# 42-PERIPHERAL_POWER_SUPPLY.net
KiCad netlist of a schematic drawn in Altium Designer
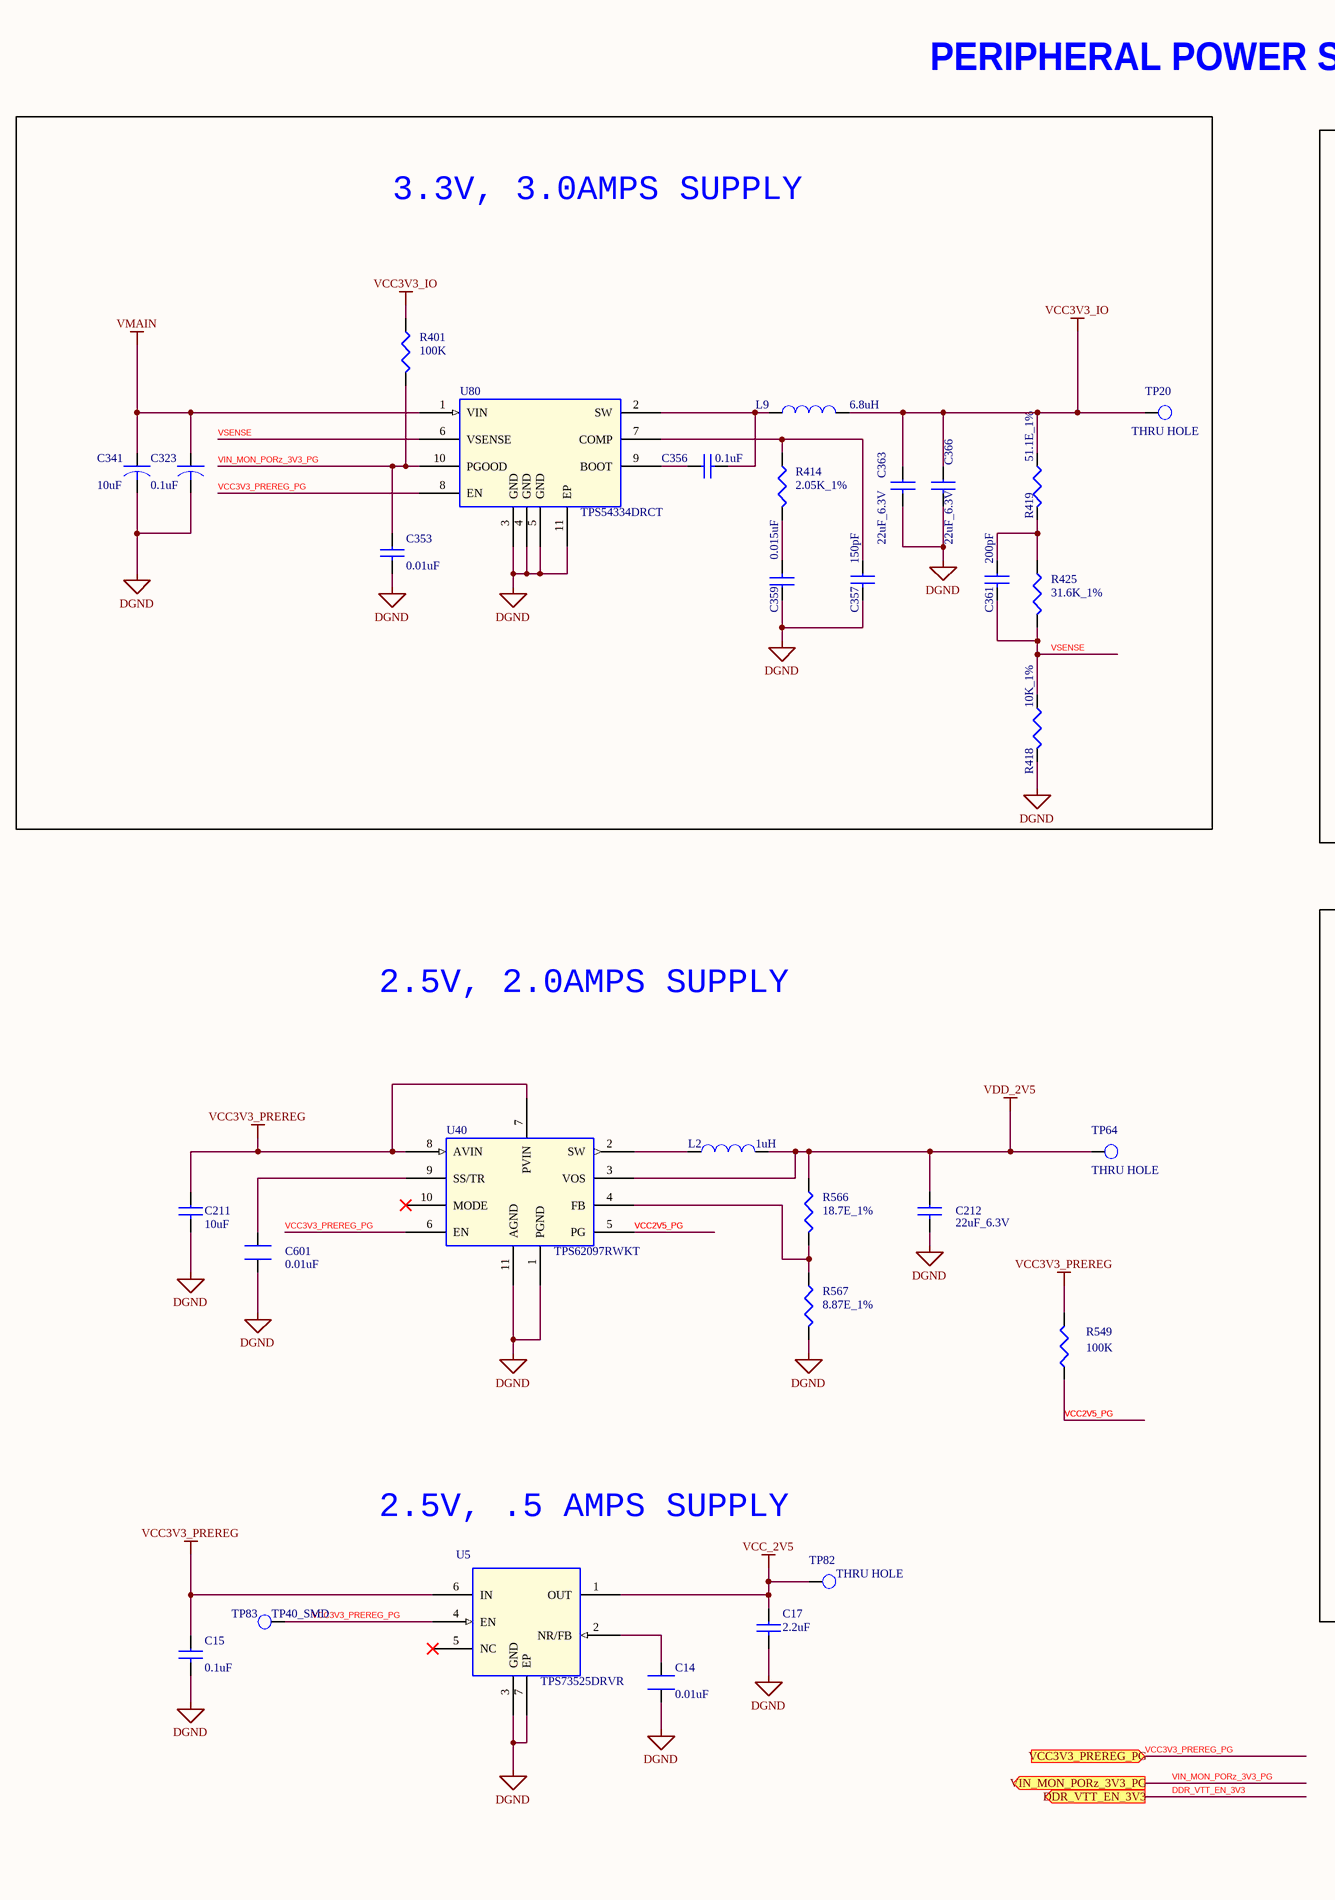
[diagram p0: 42-PERIPHERAL POWER SUPPLY.SchDoc, left]
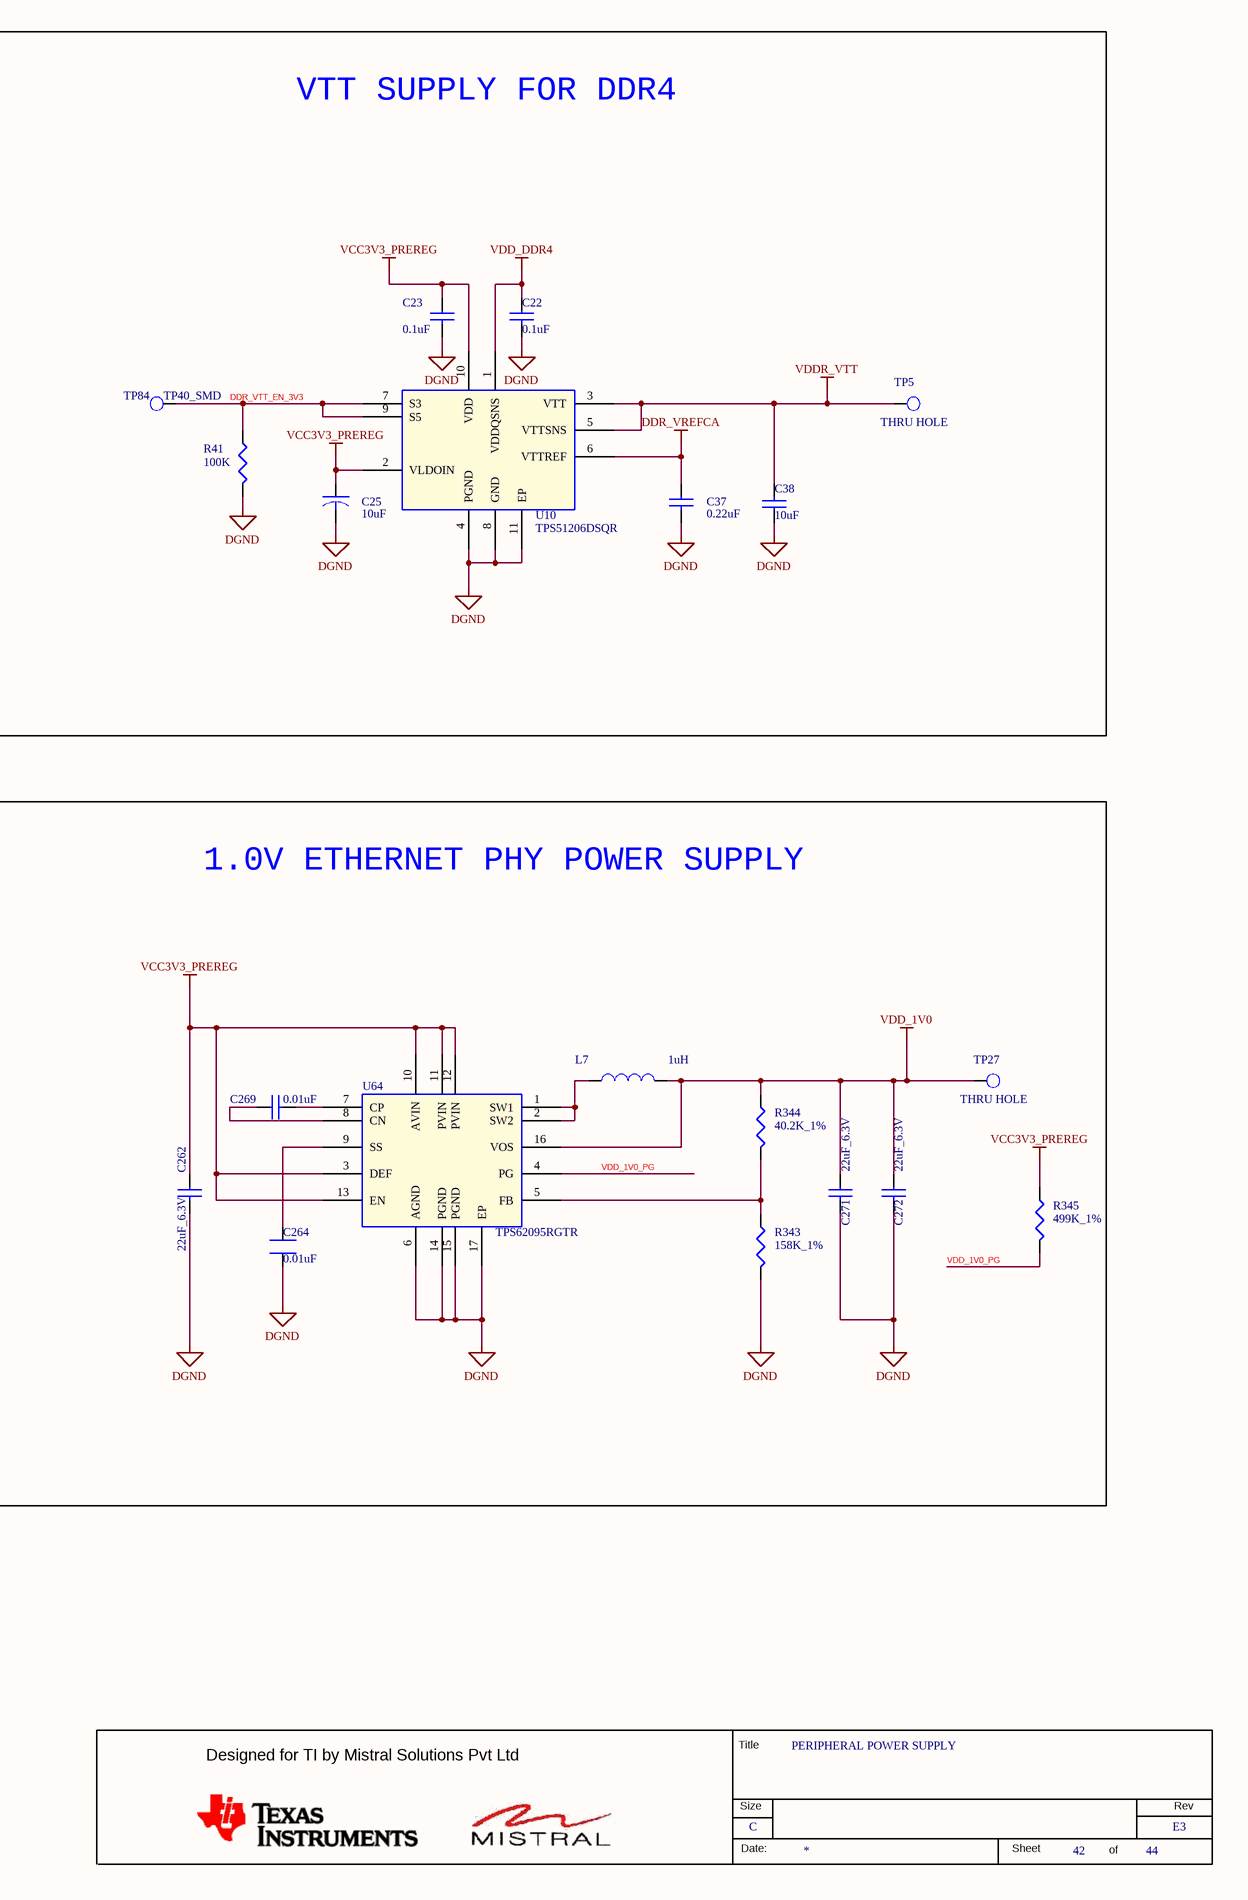
[diagram p1: 42-PERIPHERAL POWER SUPPLY.SchDoc, right]

(export (version "E")
  (design (tool "Eeschema 10.0.6"))
  (components
    (comp (ref "C14")
      (value "0.01uF")
      (footprint "TMDX654GPEVM_BRD:CAP0201_0-5")
      (description "CAP CERAMIC 0.01uF 25V 10% X5R 0201")
      (fields (field (name "DISTRIBUTOR_PART_NUMBER") "GRM033R61E103KA12J-ND") (field (name "VOLTAGE") "25V"))
      (libsource (lib "*") (part "CAP_Dup3"))
    )
    (comp (ref "C15")
      (value "0.1uF")
      (footprint "CAP0201_0-5")
      (description "CAP CERAMIC 0.1uF 16V 10% X5R 0201")
      (fields
        (field (name "MISTRAL PART NO") "120009030072-R")
        (field (name "MFR_PART_NUMBER") "GRM033R61C104KE84J")
      )
      (libsource (lib "*") (part "CAP_Dup5"))
    )
    (comp (ref "C17")
      (value "2.2uF")
      (footprint "CAP0402_0-75")
      (description "CAP CERAMIC 2.2uF 10V 20% X5R 0402")
      (fields
        (field (name "MISTRAL PART NO") "120018010016-R")
        (field (name "MFR_PART_NUMBER") "GRT155R61A225ME01D")
      )
      (libsource (lib "*") (part "CAP_Dup5"))
    )
    (comp (ref "C22")
      (value "0.1uF")
      (footprint "CAP0201_0-5")
      (description "CAP CERAMIC 0.1uF 16V 10% X5R 0201")
      (fields (field (name "DISTRIBUTOR_PART_NUMBER") "490-16742-1-ND") (field (name "VOLTAGE") "16V"))
      (libsource (lib "*") (part "CAP_Dup5"))
    )
    (comp (ref "C23")
      (value "0.1uF")
      (footprint "CAP0201_0-5")
      (description "CAP CERAMIC 0.1uF 16V 10% X5R 0201")
      (fields (field (name "DISTRIBUTOR_PART_NUMBER") "490-16742-1-ND") (field (name "VOLTAGE") "16V"))
      (libsource (lib "*") (part "CAP_Dup5"))
    )
    (comp (ref "C25")
      (value "10uF")
      (footprint "CAP0603_1")
      (description "CAP CERAMIC 10uF 10V 10% X5R 0603")
      (fields
        (field (name "MISTRAL PART NO") "120010080001-R")
        (field (name "MFR_PART_NUMBER") "0603ZD106KAT2A")
      )
      (libsource (lib "*") (part "CAP"))
    )
    (comp (ref "C37")
      (value "0.22uF")
      (footprint "CAP0402_0-75")
      (description "CAP CERAMIC 0.22uF 10V 10% X5R 0402")
      (fields
        (field (name "MISTRAL PART NO") "120009030090-R")
        (field (name "MFR_PART_NUMBER") "GRM155R61A224KE19D")
      )
      (libsource (lib "*") (part "CAP_Dup5"))
    )
    (comp (ref "C38")
      (value "10uF")
      (footprint "CAP0603_1")
      (description "CAP CERAMIC 10uF 10V 10% X5R 0603")
      (fields
        (field (name "MISTRAL PART NO") "120010080001-R")
        (field (name "MFR_PART_NUMBER") "0603ZD106KAT2A")
      )
      (libsource (lib "*") (part "CAP_Dup5"))
    )
    (comp (ref "C211")
      (value "10uF")
      (footprint "CAP0603_1")
      (description "CAP CERAMIC 10uF 10V 10% X5R 0603")
      (fields
        (field (name "MISTRAL PART NO") "120010080001-R")
        (field (name "MFR_PART_NUMBER") "0603ZD106KAT2A")
      )
      (libsource (lib "*") (part "CAP_Dup5"))
    )
    (comp (ref "C212")
      (value "22uF_6.3V")
      (footprint "CAP0603")
      (description "CAP CERAMIC 22uF 6.3V 20% X5R 0603")
      (fields
        (field (name "MISTRAL PART NO") "120015090007-R")
        (field (name "MFR_PART_NUMBER") "GRM188R60J226MEA0")
      )
      (libsource (lib "*") (part "CAP_Dup5"))
    )
    (comp (ref "C262")
      (value "22uF_6.3V")
      (footprint "CAP0603")
      (description "CAP CERAMIC 22uF 6.3V 20% X5R 0603")
      (fields (field (name "DISTRIBUTOR_PART_NUMBER") "490-7611-2-ND") (field (name "VOLTAGE") "6.3V"))
      (libsource (lib "*") (part "CAP_Dup5"))
    )
    (comp (ref "C264")
      (value "0.01uF")
      (footprint "TMDX654GPEVM_BRD:CAP0201_0-5")
      (description "CAP CERAMIC 0.01uF 25V 10% X5R 0201")
      (fields
        (field (name "MISTRAL PART NO") "120018010007-R")
        (field (name "MFR_PART_NUMBER") "GRM033R61E103KA12J")
      )
      (libsource (lib "*") (part "CAP_Dup3"))
    )
    (comp (ref "C269")
      (value "0.01uF")
      (footprint "CAP0201_0-5")
      (description "CAP CERAMIC 0.01uF 25V 10% X5R 0201")
      (fields
        (field (name "MISTRAL PART NO") "120018010007-R")
        (field (name "MFR_PART_NUMBER") "GRM033R61E103KA12J")
      )
      (libsource (lib "*") (part "CAP_Dup4"))
    )
    (comp (ref "C271")
      (value "22uF_6.3V")
      (footprint "CAP0603")
      (description "CAP CERAMIC 22uF 6.3V 20% X5R 0603")
      (fields
        (field (name "MISTRAL PART NO") "120015090007-R")
        (field (name "MFR_PART_NUMBER") "GRM188R60J226MEA0")
      )
      (libsource (lib "*") (part "CAP_Dup5"))
    )
    (comp (ref "C272")
      (value "22uF_6.3V")
      (footprint "CAP0603")
      (description "CAP CERAMIC 22uF 6.3V 20% X5R 0603")
      (fields (field (name "DISTRIBUTOR_PART_NUMBER") "490-7611-2-ND") (field (name "VOLTAGE") "6.3V"))
      (libsource (lib "*") (part "CAP_Dup5"))
    )
    (comp (ref "C323")
      (value "0.1uF")
      (footprint "CAP0603_1")
      (description "CAP CERAMIC 0.1uF 50V 20% X7R 0603")
      (fields (field (name "DISTRIBUTOR_PART_NUMBER") "399-7845-1-ND") (field (name "VOLTAGE") "50V"))
      (libsource (lib "*") (part "CAP_Dup1"))
    )
    (comp (ref "C341")
      (value "10uF")
      (footprint "CAP1206_2")
      (description "CAP CERAMIC 10uF 50V 20% X5R 1206")
      (fields (field (name "DISTRIBUTOR_PART_NUMBER") "490-10756-1-ND") (field (name "VOLTAGE") "50V"))
      (libsource (lib "*") (part "CAP"))
    )
    (comp (ref "C353")
      (value "0.01uF")
      (footprint "CAP0201_0-5")
      (description "CAP CERAMIC 0.01uF 25V 10% X5R 0201")
      (fields (field (name "DISTRIBUTOR_PART_NUMBER") "GRM033R61E103KA12J-ND") (field (name "VOLTAGE") "25V"))
      (libsource (lib "*") (part "CAP_Dup5"))
    )
    (comp (ref "C356")
      (value "0.1uF")
      (footprint "CAP0201_0-5")
      (description "CAP CERAMIC 0.1uF 16V 10% X5R 0201")
      (fields
        (field (name "MISTRAL PART NO") "120009030072-R")
        (field (name "MFR_PART_NUMBER") "GRM033R61C104KE84J")
      )
      (libsource (lib "*") (part "CAP_Dup5"))
    )
    (comp (ref "C357")
      (value "150pF")
      (footprint "CAP0402_0-75")
      (description "CAP CERAMIC 150pF 50V 10% X7R 0402")
      (fields
        (field (name "MISTRAL PART NO") "120018010022-R")
        (field (name "MFR_PART_NUMBER") "885012205056")
      )
      (libsource (lib "*") (part "CAP_Dup5"))
    )
    (comp (ref "C359")
      (value "0.015uF")
      (footprint "CAP0402")
      (description "CAP CERAMIC 0.015uF 16V 10% X7R 0402")
      (fields
        (field (name "MISTRAL PART NO") "120015120015-R")
        (field (name "MFR_PART_NUMBER") "GRM155R71C153KA01J")
      )
      (libsource (lib "*") (part "CAP_Dup5"))
    )
    (comp (ref "C361")
      (value "200pF")
      (footprint "CAP0402_0-75")
      (description "CAP CERAMIC 200pF 50V 5% C0G 0402")
      (fields (field (name "DISTRIBUTOR_PART_NUMBER") "490-3232-1-ND") (field (name "VOLTAGE") "50V"))
      (libsource (lib "*") (part "CAP_Dup5"))
    )
    (comp (ref "C363")
      (value "22uF_6.3V")
      (footprint "CAP0603")
      (description "CAP CERAMIC 22uF 6.3V 20% X5R 0603")
      (fields (field (name "DISTRIBUTOR_PART_NUMBER") "490-7611-2-ND") (field (name "VOLTAGE") "6.3V"))
      (libsource (lib "*") (part "CAP_Dup5"))
    )
    (comp (ref "C366")
      (value "22uF_6.3V")
      (footprint "CAP0603")
      (description "CAP CERAMIC 22uF 6.3V 20% X5R 0603")
      (fields (field (name "DISTRIBUTOR_PART_NUMBER") "490-7611-2-ND") (field (name "VOLTAGE") "6.3V"))
      (libsource (lib "*") (part "CAP_Dup5"))
    )
    (comp (ref "C601")
      (value "0.01uF")
      (footprint "TMDX654GPEVM_BRD:CAP0201_0-5")
      (description "CAP CERAMIC 0.01uF 25V 10% X5R 0201")
      (fields (field (name "DISTRIBUTOR_PART_NUMBER") "GRM033R61E103KA12J-ND") (field (name "VOLTAGE") "25V"))
      (libsource (lib "*") (part "CAP_Dup3"))
    )
    (comp (ref "L2")
      (value "1uH")
      (footprint "IND_IHLP2020AB_210X210_SMD_1-2")
      (description "IND POWER 1uH 4.4A 20% SMD")
      (fields
        (field (name "MISTRAL PART NO") "130017030015-R")
        (field (name "MFR_PART_NUMBER") "IHLP2020ABER1R0M01")
      )
      (libsource (lib "*") (part "INDUCTOR"))
    )
    (comp (ref "L7")
      (value "1uH")
      (footprint "IND_XFL4020_170X170_SMD_2-1")
      (description "IND POWER 1uH 8A 20% SMD")
      (fields (field (name "DISTRIBUTOR_PART_NUMBER") "994-XFL4020-102MEC") (field (name "VOLTAGE") "NA"))
      (libsource (lib "*") (part "INDUCTOR"))
    )
    (comp (ref "L9")
      (value "6.8uH")
      (footprint "IND_74439346068_260X270_SMD_6-1")
      (description "IND POWER 6.8uH 6.5A 20% SMD")
      (fields (field (name "DISTRIBUTOR_PART_NUMBER") "732-10705-1-ND") (field (name "VOLTAGE") "NA"))
      (libsource (lib "*") (part "INDUCTOR"))
    )
    (comp (ref "R41")
      (value "100K")
      (footprint "RES0402_0-5")
      (description "RES 100K 1/16W 5% 0402")
      (fields
        (field (name "MISTRAL PART NO") "110011060002-R")
        (field (name "MFR_PART_NUMBER") "CRCW0402100KJNED")
      )
      (libsource (lib "*") (part "RESISTOR_Dup4"))
    )
    (comp (ref "R343")
      (value "158K_1%")
      (footprint "RES0402_0-5")
      (description "RES 158K 1/16W 1% 0402")
      (fields (field (name "DISTRIBUTOR_PART_NUMBER") "YAG2990CT-ND") (field (name "VOLTAGE") "NA"))
      (libsource (lib "*") (part "RESISTOR_Dup5"))
    )
    (comp (ref "R344")
      (value "40.2K_1%")
      (footprint "RES0402_0-5")
      (description "RES 40.2K 1/16W 1% 0402")
      (fields
        (field (name "MISTRAL PART NO") "110009030811")
        (field (name "MFR_PART_NUMBER") "RC0402FR-0740K2L")
      )
      (libsource (lib "*") (part "RESISTOR_Dup5"))
    )
    (comp (ref "R345")
      (value "499K_1%")
      (footprint "RES0402")
      (description "RES 499K 1/16W 1% 0402")
      (fields
        (field (name "MISTRAL PART NO") "110009090015-P")
        (field (name "MFR_PART_NUMBER") "RC0402FR-07499KL")
      )
      (libsource (lib "*") (part "RESISTOR_Dup5"))
    )
    (comp (ref "R401")
      (value "100K")
      (footprint "RES0402_0-5")
      (description "RES 100K 1/16W 5% 0402")
      (fields
        (field (name "MISTRAL PART NO") "110011060002-R")
        (field (name "MFR_PART_NUMBER") "CRCW0402100KJNED")
      )
      (libsource (lib "*") (part "RESISTOR_Dup5"))
    )
    (comp (ref "R414")
      (value "2.05K_1%")
      (footprint "RES0402")
      (description "RES 2.05K 1/10W 1% 0402")
      (fields (field (name "DISTRIBUTOR_PART_NUMBER") "P2.05KLCT-ND") (field (name "VOLTAGE") "NA"))
      (libsource (lib "*") (part "RESISTOR_Dup5"))
    )
    (comp (ref "R418")
      (value "10K_1%")
      (footprint "RES0402_0-5")
      (description "RES 10K 1/16W 1% 0402")
      (fields (field (name "DISTRIBUTOR_PART_NUMBER") "311-10.0KLRTR-ND") (field (name "VOLTAGE") "NA"))
      (libsource (lib "*") (part "RESISTOR_Dup5"))
    )
    (comp (ref "R419")
      (value "51.1E_1%")
      (footprint "RES0402_0-5")
      (description "RES 51.1E 1/16W 1% 0402")
      (fields
        (field (name "MISTRAL PART NO") "110017060001-R")
        (field (name "MFR_PART_NUMBER") "RC0402FR-0751R1L")
      )
      (libsource (lib "*") (part "RESISTOR_Dup5"))
    )
    (comp (ref "R425")
      (value "31.6K_1%")
      (footprint "RES0402")
      (description "RES 31.6K 1/10W 1% 0402")
      (fields
        (field (name "MISTRAL PART NO") "110009030679-R")
        (field (name "MFR_PART_NUMBER") "ERJ-2RKF3162X")
      )
      (libsource (lib "*") (part "RESISTOR_Dup5"))
    )
    (comp (ref "R549")
      (value "100K")
      (footprint "RES0402_0-5")
      (description "RES 100K 1/16W 5% 0402")
      (fields (field (name "DISTRIBUTOR_PART_NUMBER") "541-100KJCT-ND") (field (name "VOLTAGE") "NA"))
      (libsource (lib "*") (part "RESISTOR_Dup5"))
    )
    (comp (ref "R566")
      (value "18.7E_1%")
      (footprint "RES0402")
      (description "RES 18.7E 1/16W 1% 0402")
      (fields
        (field (name "MISTRAL PART NO") "110010090023-P")
        (field (name "MFR_PART_NUMBER") "CRCW040218R7FKED")
      )
      (libsource (lib "*") (part "RESISTOR_Dup5"))
    )
    (comp (ref "R567")
      (value "8.87E_1%")
      (footprint "RES0402")
      (description "RES 8.87E 1/16W 1% 0402")
      (fields
        (field (name "MISTRAL PART NO") "110014010002-R")
        (field (name "MFR_PART_NUMBER") "CRCW04028R87FKED")
      )
      (libsource (lib "*") (part "RESISTOR_Dup5"))
    )
    (comp (ref "TP5")
      (value "THRU HOLE")
      (footprint "TP_40X65")
      (description "TESTPOINT 1.0MM DRILL PTH")
      (fields (field (name "DISTRIBUTOR_PART_NUMBER") "NA") (field (name "MFR_PART_NUMBER") "TP_40X65"))
      (libsource (lib "*") (part "TESTPOINT"))
    )
    (comp (ref "TP20")
      (value "THRU HOLE")
      (footprint "TP_40X65")
      (description "TESTPOINT 1.0MM DRILL PTH")
      (fields (field (name "DISTRIBUTOR_PART_NUMBER") "NA") (field (name "MFR_PART_NUMBER") "TP_40X65"))
      (libsource (lib "*") (part "TESTPOINT"))
    )
    (comp (ref "TP27")
      (value "THRU HOLE")
      (footprint "TP_40X65")
      (description "TESTPOINT 1.0MM DRILL PTH")
      (fields (field (name "DISTRIBUTOR_PART_NUMBER") "NA") (field (name "MFR_PART_NUMBER") "TP_40X65"))
      (libsource (lib "*") (part "TESTPOINT"))
    )
    (comp (ref "TP64")
      (value "THRU HOLE")
      (footprint "TP_40X65")
      (description "TESTPOINT 1.0MM DRILL PTH")
      (fields (field (name "MISTRAL PART NO") "130009030938") (field (name "MFR_PART_NUMBER") "TP_40X65"))
      (libsource (lib "*") (part "TESTPOINT"))
    )
    (comp (ref "TP82")
      (value "THRU HOLE")
      (footprint "TP_40X65")
      (description "TESTPOINT 1.0MM DRILL PTH")
      (fields (field (name "DISTRIBUTOR_PART_NUMBER") "NA") (field (name "MFR_PART_NUMBER") "TP_40X65"))
      (libsource (lib "*") (part "TESTPOINT"))
    )
    (comp (ref "TP83")
      (value "TP40_SMD")
      (footprint "TP40_SMD")
      (description "TESTPOINT CIR 40 SMD")
      (fields (field (name "MISTRAL PART NO") "130009030933") (field (name "DISTRIBUTOR_PART_NUMBER") "NA"))
      (libsource (lib "*") (part "TESTPOINT"))
    )
    (comp (ref "TP84")
      (value "TP40_SMD")
      (footprint "TP40_SMD")
      (description "TESTPOINT CIR 40 SMD")
      (fields (field (name "VOLTAGE") "NA") (field (name "MISTRAL PART NO") "130009030933"))
      (libsource (lib "*") (part "TESTPOINT"))
    )
    (comp (ref "U5")
      (value "TPS73525DRVR")
      (footprint "SON6_25-59_85X85_0-8")
      (description "IC 500mA LOW DROPOUT HIGH PSRR LINEAR REGULATOR SON6")
      (fields (field (name "DISTRIBUTOR_PART_NUMBER") "296-27480-1-ND") (field (name "VOLTAGE") "NA"))
      (libsource (lib "*") (part "TPS73501DRVR_SON6"))
    )
    (comp (ref "U10")
      (value "TPS51206DSQR")
      (footprint "DFN10_15-74_80X80_0-8")
      (description "IC SINK/SOURCE DDR TERMINATION REGULATOR WSON10")
      (fields (field (name "MISTRAL PART NO") "142017090016-R") (field (name "TOLERANCE") "NA"))
      (libsource (lib "*") (part "TPS51206DSQR_WSON10"))
    )
    (comp (ref "U40")
      (value "TPS62097RWKT")
      (footprint "VQFNHR11_TPS62097_80X80_1")
      (description "IC 2A SYNCHRONOUS STEP DOWN CONVERTER WITH IDCS CONTROL VQFN-HR11")
      (fields (field (name "MISTRAL PART NO") "142017090025-R") (field (name "TOLERANCE") "NA"))
      (libsource (lib "*") (part "TPS62097RWKT_VQFNHR11"))
    )
    (comp (ref "U64")
      (value "TPS62095RGTR")
      (footprint "QFN16_19-68_120X120_1")
      (description "IC 4A STEP DOWN CONVERTER WITH DCS CONTROL VQFN16")
      (fields (field (name "DISTRIBUTOR_PART_NUMBER") "296-40833-1-ND") (field (name "VOLTAGE") "NA"))
      (libsource (lib "*") (part "TPS62095RGTR_VQFN16"))
    )
    (comp (ref "U80")
      (value "TPS54334DRCT")
      (footprint "SON10_19-68_125X125_1")
      (description "IC 3A O/P CURRENT SYNCHRONOUS STEP DOWN VOLTAGE CONVERTER VSON10")
      (fields (field (name "DISTRIBUTOR_PART_NUMBER") "296-42172-2-ND") (field (name "VOLTAGE") "NA"))
      (libsource (lib "*") (part "TPS54334DRCT_VSON10"))
    )
  )
  (nets
    (net (code "1") (name "/DDR_VTT_EN_3V3") (class "Default")
      (node (ref "R41") (pin "1") (pinfunction "1_1") (pintype "passive"))
      (node (ref "TP84") (pin "1") (pinfunction "TP_1") (pintype "passive"))
      (node (ref "U10") (pin "7") (pinfunction "S3_7") (pintype "passive"))
      (node (ref "U10") (pin "9") (pinfunction "S5_9") (pintype "passive"))
    )
    (net (code "2") (name "/VCC2V5_PG") (class "Default")
      (node (ref "R549") (pin "1") (pinfunction "1_1") (pintype "passive"))
      (node (ref "U40") (pin "5") (pinfunction "PG_5") (pintype "passive"))
    )
    (net (code "3") (name "/VCC3V3_PREREG_PG") (class "Default")
      (node (ref "TP83") (pin "1") (pinfunction "TP_1") (pintype "passive"))
      (node (ref "U40") (pin "6") (pinfunction "EN_6") (pintype "passive"))
      (node (ref "U5") (pin "4") (pinfunction "EN_4") (pintype "input"))
      (node (ref "U80") (pin "8") (pinfunction "EN_8") (pintype "passive"))
    )
    (net (code "4") (name "/VDD_1V0_PG") (class "Default")
      (node (ref "R345") (pin "2") (pinfunction "2_2") (pintype "passive"))
      (node (ref "U64") (pin "4") (pinfunction "PG_4") (pintype "passive"))
    )
    (net (code "5") (name "/VIN_MON_PORz_3V3_PG") (class "Default")
      (node (ref "C353") (pin "1") (pinfunction "1_1") (pintype "passive"))
      (node (ref "R401") (pin "2") (pinfunction "2_2") (pintype "passive"))
      (node (ref "U80") (pin "10") (pinfunction "PGOOD_10") (pintype "passive"))
    )
    (net (code "6") (name "/VSENSE") (class "Default")
      (node (ref "C361") (pin "2") (pinfunction "2_2") (pintype "passive"))
      (node (ref "R418") (pin "1") (pinfunction "1_1") (pintype "passive"))
      (node (ref "R425") (pin "2") (pinfunction "2_2") (pintype "passive"))
      (node (ref "U80") (pin "6") (pinfunction "VSENSE_6") (pintype "passive"))
    )
    (net (code "7") (name "DDR_VREFCA") (class "Default")
      (node (ref "C37") (pin "1") (pinfunction "1_1") (pintype "passive"))
      (node (ref "U10") (pin "6") (pinfunction "VTTREF_6") (pintype "passive"))
    )
    (net (code "8") (name "DGND") (class "Default")
      (node (ref "C14") (pin "2") (pinfunction "2_2") (pintype "passive"))
      (node (ref "C15") (pin "2") (pinfunction "2_2") (pintype "passive"))
      (node (ref "C17") (pin "2") (pinfunction "2_2") (pintype "passive"))
      (node (ref "C211") (pin "2") (pinfunction "2_2") (pintype "passive"))
      (node (ref "C212") (pin "2") (pinfunction "2_2") (pintype "passive"))
      (node (ref "C22") (pin "2") (pinfunction "2_2") (pintype "passive"))
      (node (ref "C23") (pin "2") (pinfunction "2_2") (pintype "passive"))
      (node (ref "C25") (pin "2") (pinfunction "2_2") (pintype "passive"))
      (node (ref "C262") (pin "2") (pinfunction "2_2") (pintype "passive"))
      (node (ref "C264") (pin "2") (pinfunction "2_2") (pintype "passive"))
      (node (ref "C271") (pin "2") (pinfunction "2_2") (pintype "passive"))
      (node (ref "C272") (pin "2") (pinfunction "2_2") (pintype "passive"))
      (node (ref "C323") (pin "2") (pinfunction "2_2") (pintype "passive"))
      (node (ref "C341") (pin "2") (pinfunction "2_2") (pintype "passive"))
      (node (ref "C353") (pin "2") (pinfunction "2_2") (pintype "passive"))
      (node (ref "C357") (pin "2") (pinfunction "2_2") (pintype "passive"))
      (node (ref "C359") (pin "1") (pinfunction "1_1") (pintype "passive"))
      (node (ref "C363") (pin "2") (pinfunction "2_2") (pintype "passive"))
      (node (ref "C366") (pin "2") (pinfunction "2_2") (pintype "passive"))
      (node (ref "C37") (pin "2") (pinfunction "2_2") (pintype "passive"))
      (node (ref "C38") (pin "1") (pinfunction "1_1") (pintype "passive"))
      (node (ref "C601") (pin "2") (pinfunction "2_2") (pintype "passive"))
      (node (ref "R343") (pin "2") (pinfunction "2_2") (pintype "passive"))
      (node (ref "R41") (pin "2") (pinfunction "2_2") (pintype "passive"))
      (node (ref "R418") (pin "2") (pinfunction "2_2") (pintype "passive"))
      (node (ref "R567") (pin "2") (pinfunction "2_2") (pintype "passive"))
      (node (ref "U10") (pin "11") (pinfunction "EP_11") (pintype "power_in"))
      (node (ref "U10") (pin "4") (pinfunction "PGND_4") (pintype "power_in"))
      (node (ref "U10") (pin "8") (pinfunction "GND_8") (pintype "power_in"))
      (node (ref "U40") (pin "1") (pinfunction "PGND_1") (pintype "power_in"))
      (node (ref "U40") (pin "11") (pinfunction "AGND_11") (pintype "power_in"))
      (node (ref "U5") (pin "3") (pinfunction "GND_3") (pintype "power_in"))
      (node (ref "U5") (pin "7") (pinfunction "EP_7") (pintype "power_in"))
      (node (ref "U64") (pin "14") (pinfunction "PGND_14") (pintype "power_in"))
      (node (ref "U64") (pin "15") (pinfunction "PGND_15") (pintype "power_in"))
      (node (ref "U64") (pin "17") (pinfunction "EP_17") (pintype "power_in"))
      (node (ref "U64") (pin "6") (pinfunction "AGND_6") (pintype "power_in"))
      (node (ref "U80") (pin "11") (pinfunction "EP_11") (pintype "power_in"))
      (node (ref "U80") (pin "3") (pinfunction "GND_3") (pintype "power_in"))
      (node (ref "U80") (pin "4") (pinfunction "GND_4") (pintype "power_in"))
      (node (ref "U80") (pin "5") (pinfunction "GND_5") (pintype "power_in"))
    )
    (net (code "9") (name "Net-(C359-Pad2)") (class "Default")
      (node (ref "C359") (pin "2") (pinfunction "2_2") (pintype "passive"))
      (node (ref "R414") (pin "2") (pinfunction "2_2") (pintype "passive"))
    )
    (net (code "10") (name "Net-(C361-Pad1)") (class "Default")
      (node (ref "C361") (pin "1") (pinfunction "1_1") (pintype "passive"))
      (node (ref "R419") (pin "2") (pinfunction "2_2") (pintype "passive"))
      (node (ref "R425") (pin "1") (pinfunction "1_1") (pintype "passive"))
    )
    (net (code "11") (name "Net-(U5-NR{slash}FB)") (class "Default")
      (node (ref "C14") (pin "1") (pinfunction "1_1") (pintype "passive"))
      (node (ref "U5") (pin "2") (pinfunction "NR/FB_2") (pintype "input"))
    )
    (net (code "12") (name "Net-(U40-FB)") (class "Default")
      (node (ref "R566") (pin "2") (pinfunction "2_2") (pintype "passive"))
      (node (ref "R567") (pin "1") (pinfunction "1_1") (pintype "passive"))
      (node (ref "U40") (pin "4") (pinfunction "FB_4") (pintype "passive"))
    )
    (net (code "13") (name "Net-(U40-SS{slash}TR)") (class "Default")
      (node (ref "C601") (pin "1") (pinfunction "1_1") (pintype "passive"))
      (node (ref "U40") (pin "9") (pinfunction "SS/TR_9") (pintype "passive"))
    )
    (net (code "14") (name "Net-(U40-SW)") (class "Default")
      (node (ref "L2") (pin "1") (pinfunction "1_1") (pintype "passive"))
      (node (ref "U40") (pin "2") (pinfunction "SW_2") (pintype "output"))
    )
    (net (code "15") (name "Net-(U64-CN)") (class "Default")
      (node (ref "C269") (pin "1") (pinfunction "1_1") (pintype "passive"))
      (node (ref "U64") (pin "8") (pinfunction "CN_8") (pintype "passive"))
    )
    (net (code "16") (name "Net-(U64-CP)") (class "Default")
      (node (ref "C269") (pin "2") (pinfunction "2_2") (pintype "passive"))
      (node (ref "U64") (pin "7") (pinfunction "CP_7") (pintype "passive"))
    )
    (net (code "17") (name "Net-(U64-FB)") (class "Default")
      (node (ref "R343") (pin "1") (pinfunction "1_1") (pintype "passive"))
      (node (ref "R344") (pin "2") (pinfunction "2_2") (pintype "passive"))
      (node (ref "U64") (pin "5") (pinfunction "FB_5") (pintype "passive"))
    )
    (net (code "18") (name "Net-(U64-SS)") (class "Default")
      (node (ref "C264") (pin "1") (pinfunction "1_1") (pintype "passive"))
      (node (ref "U64") (pin "9") (pinfunction "SS_9") (pintype "passive"))
    )
    (net (code "19") (name "Net-(U64-SW1)") (class "Default")
      (node (ref "L7") (pin "1") (pinfunction "1_1") (pintype "passive"))
      (node (ref "U64") (pin "1") (pinfunction "SW1_1") (pintype "passive"))
      (node (ref "U64") (pin "2") (pinfunction "SW2_2") (pintype "passive"))
    )
    (net (code "20") (name "Net-(U80-BOOT)") (class "Default")
      (node (ref "C356") (pin "1") (pinfunction "1_1") (pintype "passive"))
      (node (ref "U80") (pin "9") (pinfunction "BOOT_9") (pintype "passive"))
    )
    (net (code "21") (name "Net-(U80-COMP)") (class "Default")
      (node (ref "C357") (pin "1") (pinfunction "1_1") (pintype "passive"))
      (node (ref "R414") (pin "1") (pinfunction "1_1") (pintype "passive"))
      (node (ref "U80") (pin "7") (pinfunction "COMP_7") (pintype "passive"))
    )
    (net (code "22") (name "Net-(U80-SW)") (class "Default")
      (node (ref "C356") (pin "2") (pinfunction "2_2") (pintype "passive"))
      (node (ref "L9") (pin "1") (pinfunction "1_1") (pintype "passive"))
      (node (ref "U80") (pin "2") (pinfunction "SW_2") (pintype "passive"))
    )
    (net (code "23") (name "VCC3V3_IO") (class "Default")
      (node (ref "C363") (pin "1") (pinfunction "1_1") (pintype "passive"))
      (node (ref "C366") (pin "1") (pinfunction "1_1") (pintype "passive"))
      (node (ref "L9") (pin "2") (pinfunction "2_2") (pintype "passive"))
      (node (ref "R401") (pin "1") (pinfunction "1_1") (pintype "passive"))
      (node (ref "R419") (pin "1") (pinfunction "1_1") (pintype "passive"))
      (node (ref "TP20") (pin "1") (pinfunction "TP_1") (pintype "passive"))
    )
    (net (code "24") (name "VCC3V3_PREREG") (class "Default")
      (node (ref "C15") (pin "1") (pinfunction "1_1") (pintype "passive"))
      (node (ref "C211") (pin "1") (pinfunction "1_1") (pintype "passive"))
      (node (ref "C23") (pin "1") (pinfunction "1_1") (pintype "passive"))
      (node (ref "C25") (pin "1") (pinfunction "1_1") (pintype "passive"))
      (node (ref "C262") (pin "1") (pinfunction "1_1") (pintype "passive"))
      (node (ref "R345") (pin "1") (pinfunction "1_1") (pintype "passive"))
      (node (ref "R549") (pin "2") (pinfunction "2_2") (pintype "passive"))
      (node (ref "U10") (pin "10") (pinfunction "VDD_10") (pintype "power_in"))
      (node (ref "U10") (pin "2") (pinfunction "VLDOIN_2") (pintype "passive"))
      (node (ref "U40") (pin "7") (pinfunction "PVIN_7") (pintype "power_in"))
      (node (ref "U40") (pin "8") (pinfunction "AVIN_8") (pintype "input"))
      (node (ref "U5") (pin "6") (pinfunction "IN_6") (pintype "power_in"))
      (node (ref "U64") (pin "10") (pinfunction "AVIN_10") (pintype "power_in"))
      (node (ref "U64") (pin "11") (pinfunction "PVIN_11") (pintype "power_in"))
      (node (ref "U64") (pin "12") (pinfunction "PVIN_12") (pintype "power_in"))
      (node (ref "U64") (pin "13") (pinfunction "EN_13") (pintype "passive"))
      (node (ref "U64") (pin "3") (pinfunction "DEF_3") (pintype "passive"))
    )
    (net (code "25") (name "VCC_2V5") (class "Default")
      (node (ref "C17") (pin "1") (pinfunction "1_1") (pintype "passive"))
      (node (ref "TP82") (pin "1") (pinfunction "TP_1") (pintype "passive"))
      (node (ref "U5") (pin "1") (pinfunction "OUT_1") (pintype "power_in"))
    )
    (net (code "26") (name "VDDR_VTT") (class "Default")
      (node (ref "C38") (pin "2") (pinfunction "2_2") (pintype "passive"))
      (node (ref "TP5") (pin "1") (pinfunction "TP_1") (pintype "passive"))
      (node (ref "U10") (pin "3") (pinfunction "VTT_3") (pintype "passive"))
      (node (ref "U10") (pin "5") (pinfunction "VTTSNS_5") (pintype "passive"))
    )
    (net (code "27") (name "VDD_1V0") (class "Default")
      (node (ref "C271") (pin "1") (pinfunction "1_1") (pintype "passive"))
      (node (ref "C272") (pin "1") (pinfunction "1_1") (pintype "passive"))
      (node (ref "L7") (pin "2") (pinfunction "2_2") (pintype "passive"))
      (node (ref "R344") (pin "1") (pinfunction "1_1") (pintype "passive"))
      (node (ref "TP27") (pin "1") (pinfunction "TP_1") (pintype "passive"))
      (node (ref "U64") (pin "16") (pinfunction "VOS_16") (pintype "passive"))
    )
    (net (code "28") (name "VDD_2V5") (class "Default")
      (node (ref "C212") (pin "1") (pinfunction "1_1") (pintype "passive"))
      (node (ref "L2") (pin "2") (pinfunction "2_2") (pintype "passive"))
      (node (ref "R566") (pin "1") (pinfunction "1_1") (pintype "passive"))
      (node (ref "TP64") (pin "1") (pinfunction "TP_1") (pintype "passive"))
      (node (ref "U40") (pin "3") (pinfunction "VOS_3") (pintype "passive"))
    )
    (net (code "29") (name "VDD_DDR4") (class "Default")
      (node (ref "C22") (pin "1") (pinfunction "1_1") (pintype "passive"))
      (node (ref "U10") (pin "1") (pinfunction "VDDQSNS_1") (pintype "power_in"))
    )
    (net (code "30") (name "VMAIN") (class "Default")
      (node (ref "C323") (pin "1") (pinfunction "1_1") (pintype "passive"))
      (node (ref "C341") (pin "1") (pinfunction "1_1") (pintype "passive"))
      (node (ref "U80") (pin "1") (pinfunction "VIN_1") (pintype "input"))
    )
    (net (code "31") (name "unconnected-(U5-NC-Pad5)") (class "Default")
      (node (ref "U5") (pin "5") (pinfunction "NC_5") (pintype "passive+no_connect"))
    )
    (net (code "32") (name "unconnected-(U40-MODE-Pad10)") (class "Default")
      (node (ref "U40") (pin "10") (pinfunction "MODE_10") (pintype "passive+no_connect"))
    )
  )
)
